# Blocky_STM_Zero.net
KiCad netlist of a schematic drawn in EAGLE
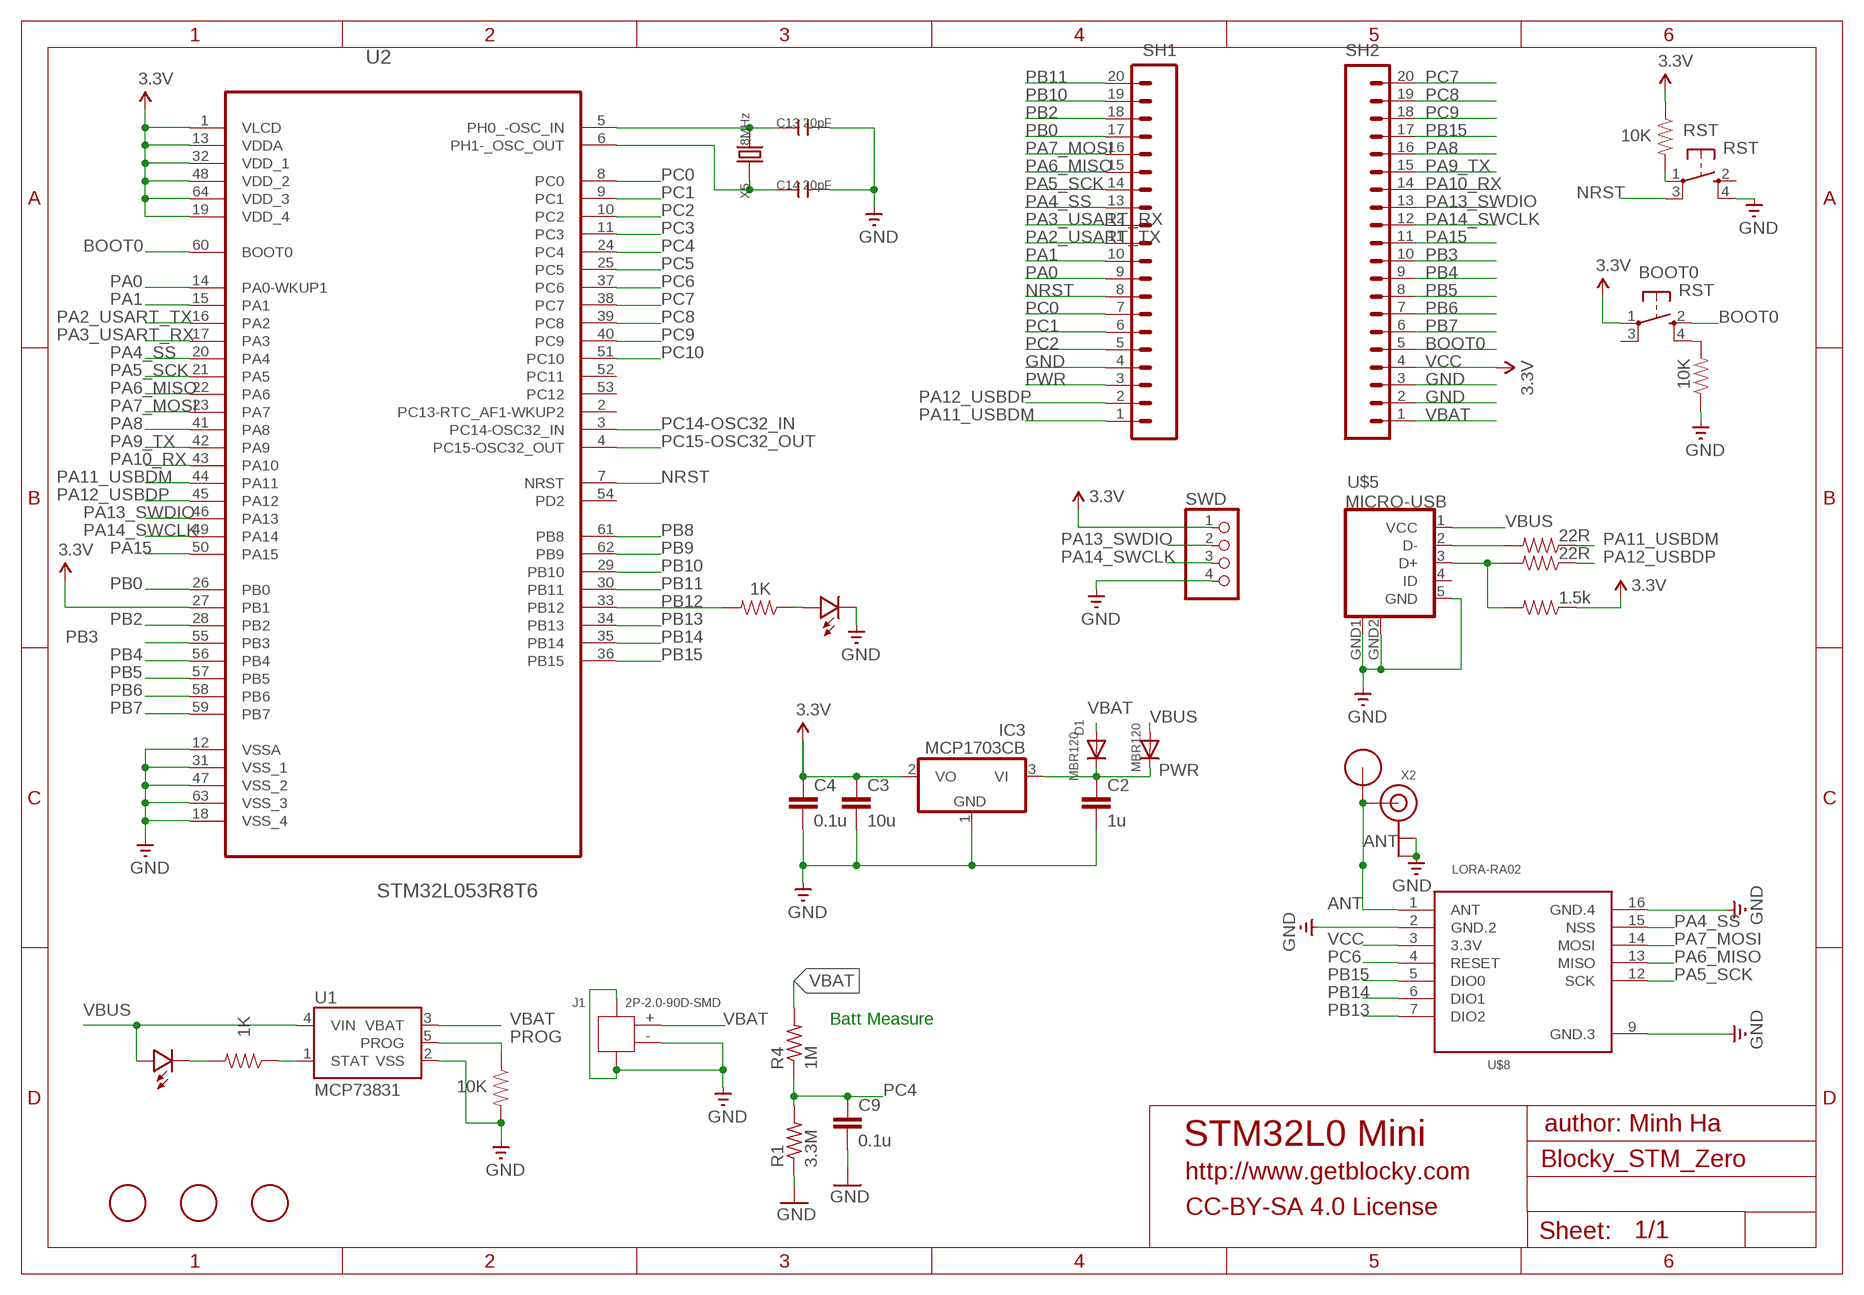
[diagram p0: schematic, sheet 1]

(export (version "E")
  (design (tool "Eeschema 10.0.6"))
  (components
    (comp (ref "BOOT0")
      (value "RST")
      (footprint "eagle-import:KMR2")
      (libsource (lib "eagle-import") (part "SPST_TACT-KMR2"))
    )
    (comp (ref "C2")
      (value "1u")
      (footprint "eagle-import:0603-CAP")
      (libsource (lib "eagle-import") (part "CAP0603-CAP"))
    )
    (comp (ref "C3")
      (value "10u")
      (footprint "eagle-import:0603-CAP")
      (libsource (lib "eagle-import") (part "CAP0603-CAP"))
    )
    (comp (ref "C4")
      (value "0.1u")
      (footprint "eagle-import:0603-CAP")
      (libsource (lib "eagle-import") (part "CAP0603-CAP"))
    )
    (comp (ref "C9")
      (value "0.1u")
      (footprint "eagle-import:0603-CAP")
      (libsource (lib "eagle-import") (part "CAP0603-CAP"))
    )
    (comp (ref "C13")
      (value "20pF")
      (footprint "eagle-import:C0603")
      (libsource (lib "eagle-import") (part "C-0603"))
    )
    (comp (ref "C14")
      (value "20pF")
      (footprint "eagle-import:C0603")
      (libsource (lib "eagle-import") (part "C-0603"))
    )
    (comp (ref "CHGR")
      (value "RED")
      (footprint "eagle-import:0603-LED")
      (libsource (lib "eagle-import") (part "LED0603"))
    )
    (comp (ref "D1")
      (value "MBR120")
      (footprint "eagle-import:SOD-123")
      (libsource (lib "eagle-import") (part "DIODESOD-123"))
    )
    (comp (ref "IC3")
      (value "MCP1703CB")
      (footprint "eagle-import:SOT23")
      (libsource (lib "eagle-import") (part "MCP1703CB"))
    )
    (comp (ref "J1")
      (value "2P-2.0-90D-SMD")
      (footprint "eagle-import:HW2-SMD-2.0-90D")
      (libsource (lib "eagle-import") (part "CONN-HEADER-SMD-PH-SIDE-(2P-2.0MM)"))
    )
    (comp (ref "MBR0001")
      (value "MBR120")
      (footprint "eagle-import:SOD-123")
      (libsource (lib "eagle-import") (part "DIODESOD-123"))
    )
    (comp (ref "R1")
      (value "3.3M")
      (footprint "eagle-import:R0603")
      (libsource (lib "eagle-import") (part "R-US_R0603"))
    )
    (comp (ref "R2")
      (value "1K")
      (footprint "eagle-import:0603-RES")
      (libsource (lib "eagle-import") (part "RESISTOR0603-RES"))
    )
    (comp (ref "R3")
      (value "22R")
      (footprint "eagle-import:0603-RES")
      (libsource (lib "eagle-import") (part "RESISTOR0603-RES"))
    )
    (comp (ref "R4")
      (value "1M")
      (footprint "eagle-import:R0603")
      (libsource (lib "eagle-import") (part "R-US_R0603"))
    )
    (comp (ref "R5")
      (value "1K")
      (footprint "eagle-import:0603-RES")
      (libsource (lib "eagle-import") (part "RESISTOR0603-RES"))
    )
    (comp (ref "R6")
      (value "10K")
      (footprint "eagle-import:0603-RES")
      (libsource (lib "eagle-import") (part "RESISTOR0603-RES"))
    )
    (comp (ref "R7")
      (value "22R")
      (footprint "eagle-import:0603-RES")
      (libsource (lib "eagle-import") (part "RESISTOR0603-RES"))
    )
    (comp (ref "R8")
      (value "1.5k")
      (footprint "eagle-import:0603-RES")
      (libsource (lib "eagle-import") (part "RESISTOR0603-RES"))
    )
    (comp (ref "R9")
      (value "10K")
      (footprint "eagle-import:0603-RES")
      (libsource (lib "eagle-import") (part "RESISTOR0603-RES"))
    )
    (comp (ref "R10")
      (value "10K")
      (footprint "eagle-import:0603-RES")
      (libsource (lib "eagle-import") (part "RESISTOR0603-RES"))
    )
    (comp (ref "RST")
      (value "RST")
      (footprint "eagle-import:KMR2")
      (libsource (lib "eagle-import") (part "SPST_TACT-KMR2"))
    )
    (comp (ref "SH1")
      (value "M20")
      (footprint "eagle-import:1X20")
      (libsource (lib "eagle-import") (part "M20"))
    )
    (comp (ref "SH2")
      (value "M20")
      (footprint "eagle-import:1X20")
      (libsource (lib "eagle-import") (part "M20"))
    )
    (comp (ref "SWD")
      (value "HEADER-1X4ROUND")
      (footprint "eagle-import:1X04_ROUND")
      (libsource (lib "eagle-import") (part "HEADER-1X4ROUND"))
    )
    (comp (ref "U$1")
      (value "RFM12B_ANTENNA")
      (footprint "eagle-import:RFM12B-ANTENNA")
      (libsource (lib "eagle-import") (part "RFM12B_ANTENNA"))
    )
    (comp (ref "U$2")
      (value "FIDUCIAL")
      (footprint "eagle-import:FIDUCIAL_1MM")
      (libsource (lib "eagle-import") (part "FIDUCIAL"))
    )
    (comp (ref "U$4")
      (value "FIDUCIAL")
      (footprint "eagle-import:FIDUCIAL_1MM")
      (libsource (lib "eagle-import") (part "FIDUCIAL"))
    )
    (comp (ref "U$5")
      (value "MICRO-USB")
      (footprint "eagle-import:MICRO-USB")
      (libsource (lib "eagle-import") (part "MICRO-USB"))
    )
    (comp (ref "U$6")
      (value "LED0603")
      (footprint "eagle-import:0603-LED")
      (libsource (lib "eagle-import") (part "LED0603"))
    )
    (comp (ref "U$7")
      (value "FIDUCIAL")
      (footprint "eagle-import:FIDUCIAL_1MM")
      (libsource (lib "eagle-import") (part "FIDUCIAL"))
    )
    (comp (ref "U$8")
      (value "LORA-RA02")
      (footprint "eagle-import:LORA-RA2-SMD")
      (libsource (lib "eagle-import") (part "LORA-RA-02-433MHZ"))
    )
    (comp (ref "U1")
      (value "MCP73831")
      (footprint "eagle-import:SOT23-5")
      (libsource (lib "eagle-import") (part "MCP73831"))
    )
    (comp (ref "U2")
      (value "STM32L053R8T6")
      (footprint "eagle-import:QFP50P1200X1200X160-64N")
      (fields (field (name "MPN") "STM32L152RBT6"))
      (libsource (lib "eagle-import") (part "STM32L152RBT6"))
    )
    (comp (ref "X2")
      (value "ANTENNA_U.FL")
      (footprint "eagle-import:U.FL")
      (libsource (lib "eagle-import") (part "ANTENNA_U.FL"))
    )
    (comp (ref "X5")
      (value "8MHz")
      (footprint "eagle-import:2P-SMD-5X3.2")
      (libsource (lib "eagle-import") (part "CRYSTAL'5032'"))
    )
  )
  (nets
    (net (code "1") (name "/ANT") (class "Default")
      (node (ref "U$1") (pin "P$1") (pinfunction "1_P$1") (pintype "bidirectional"))
      (node (ref "U$8") (pin "1") (pinfunction "ANT_1") (pintype "bidirectional"))
      (node (ref "X2") (pin "3") (pinfunction "SIGNAL_3") (pintype "passive"))
    )
    (net (code "2") (name "/BOOT0") (class "Default")
      (node (ref "BOOT0") (pin "2") (pinfunction "S_2") (pintype "passive"))
      (node (ref "SH2") (pin "5") (pinfunction "5_5") (pintype "passive"))
      (node (ref "U2") (pin "60") (pinfunction "BOOT0_60") (pintype "input"))
    )
    (net (code "3") (name "/NRST") (class "Default")
      (node (ref "RST") (pin "3") (pinfunction "P1_3") (pintype "passive"))
      (node (ref "SH1") (pin "8") (pinfunction "8_8") (pintype "passive"))
      (node (ref "U2") (pin "7") (pinfunction "NRST_7") (pintype "bidirectional"))
    )
    (net (code "4") (name "/PA0") (class "Default")
      (node (ref "SH1") (pin "9") (pinfunction "9_9") (pintype "passive"))
      (node (ref "U2") (pin "14") (pinfunction "PA0-WKUP1_14") (pintype "bidirectional"))
    )
    (net (code "5") (name "/PA1") (class "Default")
      (node (ref "SH1") (pin "10") (pinfunction "10_10") (pintype "passive"))
      (node (ref "U2") (pin "15") (pinfunction "PA1_15") (pintype "bidirectional"))
    )
    (net (code "6") (name "/PA2_USART_TX") (class "Default")
      (node (ref "SH1") (pin "11") (pinfunction "11_11") (pintype "passive"))
      (node (ref "U2") (pin "16") (pinfunction "PA2_16") (pintype "bidirectional"))
    )
    (net (code "7") (name "/PA3_USART_RX") (class "Default")
      (node (ref "SH1") (pin "12") (pinfunction "12_12") (pintype "passive"))
      (node (ref "U2") (pin "17") (pinfunction "PA3_17") (pintype "bidirectional"))
    )
    (net (code "8") (name "/PA4_SS") (class "Default")
      (node (ref "SH1") (pin "13") (pinfunction "13_13") (pintype "passive"))
      (node (ref "U$8") (pin "15") (pinfunction "NSS_15") (pintype "bidirectional"))
      (node (ref "U2") (pin "20") (pinfunction "PA4_20") (pintype "bidirectional"))
    )
    (net (code "9") (name "/PA5_SCK") (class "Default")
      (node (ref "SH1") (pin "14") (pinfunction "14_14") (pintype "passive"))
      (node (ref "U$8") (pin "12") (pinfunction "SCK_12") (pintype "bidirectional"))
      (node (ref "U2") (pin "21") (pinfunction "PA5_21") (pintype "bidirectional"))
    )
    (net (code "10") (name "/PA6_MISO") (class "Default")
      (node (ref "SH1") (pin "15") (pinfunction "15_15") (pintype "passive"))
      (node (ref "U$8") (pin "13") (pinfunction "MISO_13") (pintype "bidirectional"))
      (node (ref "U2") (pin "22") (pinfunction "PA6_22") (pintype "bidirectional"))
    )
    (net (code "11") (name "/PA7_MOSI") (class "Default")
      (node (ref "SH1") (pin "16") (pinfunction "16_16") (pintype "passive"))
      (node (ref "U$8") (pin "14") (pinfunction "MOSI_14") (pintype "bidirectional"))
      (node (ref "U2") (pin "23") (pinfunction "PA7_23") (pintype "bidirectional"))
    )
    (net (code "12") (name "/PA8") (class "Default")
      (node (ref "SH2") (pin "16") (pinfunction "16_16") (pintype "passive"))
      (node (ref "U2") (pin "41") (pinfunction "PA8_41") (pintype "bidirectional"))
    )
    (net (code "13") (name "/PA9_TX") (class "Default")
      (node (ref "SH2") (pin "15") (pinfunction "15_15") (pintype "passive"))
      (node (ref "U2") (pin "42") (pinfunction "PA9_42") (pintype "bidirectional"))
    )
    (net (code "14") (name "/PA10_RX") (class "Default")
      (node (ref "SH2") (pin "14") (pinfunction "14_14") (pintype "passive"))
      (node (ref "U2") (pin "43") (pinfunction "PA10_43") (pintype "bidirectional"))
    )
    (net (code "15") (name "/PA11_USBDM") (class "Default")
      (node (ref "R3") (pin "1") (pinfunction "1_1") (pintype "passive"))
      (node (ref "SH1") (pin "1") (pinfunction "1_1") (pintype "passive"))
      (node (ref "U2") (pin "44") (pinfunction "PA11_44") (pintype "bidirectional"))
    )
    (net (code "16") (name "/PA12_USBDP") (class "Default")
      (node (ref "R7") (pin "1") (pinfunction "1_1") (pintype "passive"))
      (node (ref "SH1") (pin "2") (pinfunction "2_2") (pintype "passive"))
      (node (ref "U2") (pin "45") (pinfunction "PA12_45") (pintype "bidirectional"))
    )
    (net (code "17") (name "/PA13_SWDIO") (class "Default")
      (node (ref "SH2") (pin "13") (pinfunction "13_13") (pintype "passive"))
      (node (ref "SWD") (pin "2") (pinfunction "2_2") (pintype "passive"))
      (node (ref "U2") (pin "46") (pinfunction "PA13_46") (pintype "bidirectional"))
    )
    (net (code "18") (name "/PA14_SWCLK") (class "Default")
      (node (ref "SH2") (pin "12") (pinfunction "12_12") (pintype "passive"))
      (node (ref "SWD") (pin "3") (pinfunction "3_3") (pintype "passive"))
      (node (ref "U2") (pin "49") (pinfunction "PA14_49") (pintype "bidirectional"))
    )
    (net (code "19") (name "/PA15") (class "Default")
      (node (ref "SH2") (pin "11") (pinfunction "11_11") (pintype "passive"))
      (node (ref "U2") (pin "50") (pinfunction "PA15_50") (pintype "bidirectional"))
    )
    (net (code "20") (name "/PB0") (class "Default")
      (node (ref "SH1") (pin "17") (pinfunction "17_17") (pintype "passive"))
      (node (ref "U2") (pin "26") (pinfunction "PB0_26") (pintype "bidirectional"))
    )
    (net (code "21") (name "/PB2") (class "Default")
      (node (ref "SH1") (pin "18") (pinfunction "18_18") (pintype "passive"))
      (node (ref "U2") (pin "28") (pinfunction "PB2_28") (pintype "bidirectional"))
    )
    (net (code "22") (name "/PB3") (class "Default")
      (node (ref "SH2") (pin "10") (pinfunction "10_10") (pintype "passive"))
      (node (ref "U2") (pin "55") (pinfunction "PB3_55") (pintype "bidirectional"))
    )
    (net (code "23") (name "/PB4") (class "Default")
      (node (ref "SH2") (pin "9") (pinfunction "9_9") (pintype "passive"))
      (node (ref "U2") (pin "56") (pinfunction "PB4_56") (pintype "bidirectional"))
    )
    (net (code "24") (name "/PB5") (class "Default")
      (node (ref "SH2") (pin "8") (pinfunction "8_8") (pintype "passive"))
      (node (ref "U2") (pin "57") (pinfunction "PB5_57") (pintype "bidirectional"))
    )
    (net (code "25") (name "/PB6") (class "Default")
      (node (ref "SH2") (pin "7") (pinfunction "7_7") (pintype "passive"))
      (node (ref "U2") (pin "58") (pinfunction "PB6_58") (pintype "bidirectional"))
    )
    (net (code "26") (name "/PB7") (class "Default")
      (node (ref "SH2") (pin "6") (pinfunction "6_6") (pintype "passive"))
      (node (ref "U2") (pin "59") (pinfunction "PB7_59") (pintype "bidirectional"))
    )
    (net (code "27") (name "/PB8") (class "Default")
      (node (ref "U2") (pin "61") (pinfunction "PB8_61") (pintype "bidirectional"))
    )
    (net (code "28") (name "/PB9") (class "Default")
      (node (ref "U2") (pin "62") (pinfunction "PB9_62") (pintype "bidirectional"))
    )
    (net (code "29") (name "/PB10") (class "Default")
      (node (ref "SH1") (pin "19") (pinfunction "19_19") (pintype "passive"))
      (node (ref "U2") (pin "29") (pinfunction "PB10_29") (pintype "bidirectional"))
    )
    (net (code "30") (name "/PB11") (class "Default")
      (node (ref "SH1") (pin "20") (pinfunction "20_20") (pintype "passive"))
      (node (ref "U2") (pin "30") (pinfunction "PB11_30") (pintype "bidirectional"))
    )
    (net (code "31") (name "/PB12") (class "Default")
      (node (ref "R2") (pin "2") (pinfunction "2_2") (pintype "passive"))
      (node (ref "U2") (pin "33") (pinfunction "PB12_33") (pintype "bidirectional"))
    )
    (net (code "32") (name "/PB13") (class "Default")
      (node (ref "U$8") (pin "7") (pinfunction "DIO2_7") (pintype "bidirectional"))
      (node (ref "U2") (pin "34") (pinfunction "PB13_34") (pintype "bidirectional"))
    )
    (net (code "33") (name "/PB14") (class "Default")
      (node (ref "U$8") (pin "6") (pinfunction "DIO1_6") (pintype "bidirectional"))
      (node (ref "U2") (pin "35") (pinfunction "PB14_35") (pintype "bidirectional"))
    )
    (net (code "34") (name "/PB15") (class "Default")
      (node (ref "SH2") (pin "17") (pinfunction "17_17") (pintype "passive"))
      (node (ref "U$8") (pin "5") (pinfunction "DIO0_5") (pintype "bidirectional"))
      (node (ref "U2") (pin "36") (pinfunction "PB15_36") (pintype "bidirectional"))
    )
    (net (code "35") (name "/PC0") (class "Default")
      (node (ref "SH1") (pin "7") (pinfunction "7_7") (pintype "passive"))
      (node (ref "U2") (pin "8") (pinfunction "PC0_8") (pintype "bidirectional"))
    )
    (net (code "36") (name "/PC1") (class "Default")
      (node (ref "SH1") (pin "6") (pinfunction "6_6") (pintype "passive"))
      (node (ref "U2") (pin "9") (pinfunction "PC1_9") (pintype "bidirectional"))
    )
    (net (code "37") (name "/PC2") (class "Default")
      (node (ref "SH1") (pin "5") (pinfunction "5_5") (pintype "passive"))
      (node (ref "U2") (pin "10") (pinfunction "PC2_10") (pintype "bidirectional"))
    )
    (net (code "38") (name "/PC3") (class "Default")
      (node (ref "U2") (pin "11") (pinfunction "PC3_11") (pintype "bidirectional"))
    )
    (net (code "39") (name "/PC4") (class "Default")
      (node (ref "C9") (pin "1") (pinfunction "1_1") (pintype "passive"))
      (node (ref "R1") (pin "2") (pinfunction "2_2") (pintype "passive"))
      (node (ref "R4") (pin "1") (pinfunction "1_1") (pintype "passive"))
      (node (ref "U2") (pin "24") (pinfunction "PC4_24") (pintype "bidirectional"))
    )
    (net (code "40") (name "/PC5") (class "Default")
      (node (ref "U2") (pin "25") (pinfunction "PC5_25") (pintype "bidirectional"))
    )
    (net (code "41") (name "/PC6") (class "Default")
      (node (ref "U$8") (pin "4") (pinfunction "RESET_4") (pintype "bidirectional"))
      (node (ref "U2") (pin "37") (pinfunction "PC6_37") (pintype "bidirectional"))
    )
    (net (code "42") (name "/PC7") (class "Default")
      (node (ref "SH2") (pin "20") (pinfunction "20_20") (pintype "passive"))
      (node (ref "U2") (pin "38") (pinfunction "PC7_38") (pintype "bidirectional"))
    )
    (net (code "43") (name "/PC8") (class "Default")
      (node (ref "SH2") (pin "19") (pinfunction "19_19") (pintype "passive"))
      (node (ref "U2") (pin "39") (pinfunction "PC8_39") (pintype "bidirectional"))
    )
    (net (code "44") (name "/PC9") (class "Default")
      (node (ref "SH2") (pin "18") (pinfunction "18_18") (pintype "passive"))
      (node (ref "U2") (pin "40") (pinfunction "PC9_40") (pintype "bidirectional"))
    )
    (net (code "45") (name "/PC10") (class "Default")
      (node (ref "U2") (pin "51") (pinfunction "PC10_51") (pintype "bidirectional"))
    )
    (net (code "46") (name "/PC14-OSC32_IN") (class "Default")
      (node (ref "U2") (pin "3") (pinfunction "PC14-OSC32_IN_3") (pintype "bidirectional"))
    )
    (net (code "47") (name "/PC15-OSC32_OUT") (class "Default")
      (node (ref "U2") (pin "4") (pinfunction "PC15-OSC32_OUT_4") (pintype "bidirectional"))
    )
    (net (code "48") (name "/PROG") (class "Default")
      (node (ref "R6") (pin "1") (pinfunction "1_1") (pintype "passive"))
      (node (ref "U1") (pin "5") (pinfunction "PROG_5") (pintype "input"))
    )
    (net (code "49") (name "/PWR") (class "Default")
      (node (ref "C2") (pin "1") (pinfunction "1_1") (pintype "passive"))
      (node (ref "D1") (pin "C") (pinfunction "C_C") (pintype "passive"))
      (node (ref "IC3") (pin "3") (pinfunction "VI_3") (pintype "input"))
      (node (ref "MBR0001") (pin "C") (pinfunction "C_C") (pintype "passive"))
      (node (ref "SH1") (pin "3") (pinfunction "3_3") (pintype "passive"))
    )
    (net (code "50") (name "/VBUS") (class "Default")
      (node (ref "CHGR") (pin "PLUS") (pinfunction "PLUS_PLUS") (pintype "passive"))
      (node (ref "MBR0001") (pin "A") (pinfunction "A_A") (pintype "passive"))
      (node (ref "U$5") (pin "1") (pinfunction "VCC_1") (pintype "power_in"))
      (node (ref "U1") (pin "4") (pinfunction "VIN_4") (pintype "power_in"))
    )
    (net (code "51") (name "3.3V") (class "Default")
      (node (ref "BOOT0") (pin "1") (pinfunction "P_1") (pintype "passive"))
      (node (ref "C3") (pin "1") (pinfunction "1_1") (pintype "passive"))
      (node (ref "C4") (pin "1") (pinfunction "1_1") (pintype "passive"))
      (node (ref "IC3") (pin "2") (pinfunction "VO_2") (pintype "passive"))
      (node (ref "R10") (pin "1") (pinfunction "1_1") (pintype "passive"))
      (node (ref "R8") (pin "1") (pinfunction "1_1") (pintype "passive"))
      (node (ref "SH2") (pin "4") (pinfunction "4_4") (pintype "passive"))
      (node (ref "SWD") (pin "1") (pinfunction "1_1") (pintype "passive"))
      (node (ref "U$8") (pin "3") (pinfunction "3.3V_3") (pintype "power_in"))
      (node (ref "U2") (pin "1") (pinfunction "VLCD_1") (pintype "power_in"))
      (node (ref "U2") (pin "13") (pinfunction "VDDA_13") (pintype "power_in"))
      (node (ref "U2") (pin "19") (pinfunction "VDD_4_19") (pintype "power_in"))
      (node (ref "U2") (pin "27") (pinfunction "PB1_27") (pintype "bidirectional"))
      (node (ref "U2") (pin "32") (pinfunction "VDD_1_32") (pintype "power_in"))
      (node (ref "U2") (pin "48") (pinfunction "VDD_2_48") (pintype "power_in"))
      (node (ref "U2") (pin "64") (pinfunction "VDD_3_64") (pintype "power_in"))
    )
    (net (code "52") (name "GND") (class "Default")
      (node (ref "C13") (pin "2") (pinfunction "2_2") (pintype "passive"))
      (node (ref "C14") (pin "2") (pinfunction "2_2") (pintype "passive"))
      (node (ref "C2") (pin "2") (pinfunction "2_2") (pintype "passive"))
      (node (ref "C3") (pin "2") (pinfunction "2_2") (pintype "passive"))
      (node (ref "C4") (pin "2") (pinfunction "2_2") (pintype "passive"))
      (node (ref "C9") (pin "2") (pinfunction "2_2") (pintype "passive"))
      (node (ref "IC3") (pin "1") (pinfunction "GND_1") (pintype "passive"))
      (node (ref "J1") (pin "-") (pinfunction "2_-") (pintype "bidirectional"))
      (node (ref "J1") (pin "3") (pinfunction "3_3") (pintype "bidirectional"))
      (node (ref "J1") (pin "4") (pinfunction "4_4") (pintype "bidirectional"))
      (node (ref "R1") (pin "1") (pinfunction "1_1") (pintype "passive"))
      (node (ref "R6") (pin "2") (pinfunction "2_2") (pintype "passive"))
      (node (ref "R9") (pin "1") (pinfunction "1_1") (pintype "passive"))
      (node (ref "RST") (pin "4") (pinfunction "S1_4") (pintype "passive"))
      (node (ref "SH1") (pin "4") (pinfunction "4_4") (pintype "passive"))
      (node (ref "SH2") (pin "2") (pinfunction "2_2") (pintype "passive"))
      (node (ref "SH2") (pin "3") (pinfunction "3_3") (pintype "passive"))
      (node (ref "SWD") (pin "4") (pinfunction "4_4") (pintype "passive"))
      (node (ref "U$5") (pin "5") (pinfunction "GND_5") (pintype "power_in"))
      (node (ref "U$5") (pin "GND1") (pinfunction "GND_GND1") (pintype "power_in"))
      (node (ref "U$5") (pin "GND2") (pinfunction "GND_GND2") (pintype "power_in"))
      (node (ref "U$6") (pin "MINUS") (pinfunction "MINUS_MINUS") (pintype "passive"))
      (node (ref "U$8") (pin "16") (pinfunction "GND.4_16") (pintype "power_in"))
      (node (ref "U$8") (pin "2") (pinfunction "GND.2_2") (pintype "power_in"))
      (node (ref "U$8") (pin "9") (pinfunction "GND.3_9") (pintype "power_in"))
      (node (ref "U1") (pin "2") (pinfunction "VSS_2") (pintype "power_in"))
      (node (ref "U2") (pin "12") (pinfunction "VSSA_12") (pintype "power_in"))
      (node (ref "U2") (pin "18") (pinfunction "VSS_4_18") (pintype "power_in"))
      (node (ref "U2") (pin "31") (pinfunction "VSS_1_31") (pintype "power_in"))
      (node (ref "U2") (pin "47") (pinfunction "VSS_2_47") (pintype "power_in"))
      (node (ref "U2") (pin "63") (pinfunction "VSS_3_63") (pintype "power_in"))
      (node (ref "X2") (pin "1") (pinfunction "GND_1") (pintype "passive"))
      (node (ref "X2") (pin "2") (pinfunction "GND_2") (pintype "passive"))
    )
    (net (code "53") (name "Net-(BOOT0-S1)") (class "Default")
      (node (ref "BOOT0") (pin "4") (pinfunction "S1_4") (pintype "passive"))
      (node (ref "R9") (pin "2") (pinfunction "2_2") (pintype "passive"))
    )
    (net (code "54") (name "Net-(CHGR-PadMINUS)") (class "Default")
      (node (ref "CHGR") (pin "MINUS") (pinfunction "MINUS_MINUS") (pintype "passive"))
      (node (ref "R5") (pin "2") (pinfunction "2_2") (pintype "passive"))
    )
    (net (code "55") (name "Net-(R2-Pad1)") (class "Default")
      (node (ref "R2") (pin "1") (pinfunction "1_1") (pintype "passive"))
      (node (ref "U$6") (pin "PLUS") (pinfunction "PLUS_PLUS") (pintype "passive"))
    )
    (net (code "56") (name "Net-(RST-P)") (class "Default")
      (node (ref "R10") (pin "2") (pinfunction "2_2") (pintype "passive"))
      (node (ref "RST") (pin "1") (pinfunction "P_1") (pintype "passive"))
    )
    (net (code "57") (name "Net-(U$5-D+)") (class "Default")
      (node (ref "R7") (pin "2") (pinfunction "2_2") (pintype "passive"))
      (node (ref "R8") (pin "2") (pinfunction "2_2") (pintype "passive"))
      (node (ref "U$5") (pin "3") (pinfunction "D+_3") (pintype "bidirectional"))
    )
    (net (code "58") (name "Net-(U$5-D-)") (class "Default")
      (node (ref "R3") (pin "2") (pinfunction "2_2") (pintype "passive"))
      (node (ref "U$5") (pin "2") (pinfunction "D-_2") (pintype "bidirectional"))
    )
    (net (code "59") (name "Net-(U1-STAT)") (class "Default")
      (node (ref "R5") (pin "1") (pinfunction "1_1") (pintype "passive"))
      (node (ref "U1") (pin "1") (pinfunction "STAT_1") (pintype "output"))
    )
    (net (code "60") (name "Net-(U2-PH0_-OSC_IN)") (class "Default")
      (node (ref "C13") (pin "1") (pinfunction "1_1") (pintype "passive"))
      (node (ref "U2") (pin "5") (pinfunction "PH0_-OSC_IN_5") (pintype "bidirectional"))
      (node (ref "X5") (pin "2") (pinfunction "2_2") (pintype "passive"))
    )
    (net (code "61") (name "Net-(U2-PH1-_OSC_OUT)") (class "Default")
      (node (ref "C14") (pin "1") (pinfunction "1_1") (pintype "passive"))
      (node (ref "U2") (pin "6") (pinfunction "PH1-_OSC_OUT_6") (pintype "bidirectional"))
      (node (ref "X5") (pin "1") (pinfunction "1_1") (pintype "passive"))
    )
    (net (code "62") (name "VBAT") (class "Default")
      (node (ref "D1") (pin "A") (pinfunction "A_A") (pintype "passive"))
      (node (ref "J1") (pin "+") (pinfunction "1_+") (pintype "bidirectional"))
      (node (ref "R4") (pin "2") (pinfunction "2_2") (pintype "passive"))
      (node (ref "SH2") (pin "1") (pinfunction "1_1") (pintype "passive"))
      (node (ref "U1") (pin "3") (pinfunction "VBAT_3") (pintype "power_in"))
    )
    (net (code "63") (name "unconnected-(BOOT0-P1-Pad3)") (class "Default")
      (node (ref "BOOT0") (pin "3") (pinfunction "P1_3") (pintype "passive"))
    )
    (net (code "64") (name "unconnected-(RST-S-Pad2)") (class "Default")
      (node (ref "RST") (pin "2") (pinfunction "S_2") (pintype "passive"))
    )
    (net (code "65") (name "unconnected-(U$5-ID-Pad4)") (class "Default")
      (node (ref "U$5") (pin "4") (pinfunction "ID_4") (pintype "bidirectional"))
    )
    (net (code "66") (name "unconnected-(U2-PC11-Pad52)") (class "Default")
      (node (ref "U2") (pin "52") (pinfunction "PC11_52") (pintype "bidirectional"))
    )
    (net (code "67") (name "unconnected-(U2-PC12-Pad53)") (class "Default")
      (node (ref "U2") (pin "53") (pinfunction "PC12_53") (pintype "bidirectional"))
    )
    (net (code "68") (name "unconnected-(U2-PC13-RTC_AF1-WKUP2-Pad2)") (class "Default")
      (node (ref "U2") (pin "2") (pinfunction "PC13-RTC_AF1-WKUP2_2") (pintype "bidirectional"))
    )
    (net (code "69") (name "unconnected-(U2-PD2-Pad54)") (class "Default")
      (node (ref "U2") (pin "54") (pinfunction "PD2_54") (pintype "bidirectional"))
    )
  )
)
